# Synch_Demod.net
KiCad netlist of a schematic drawn in Altium Designer
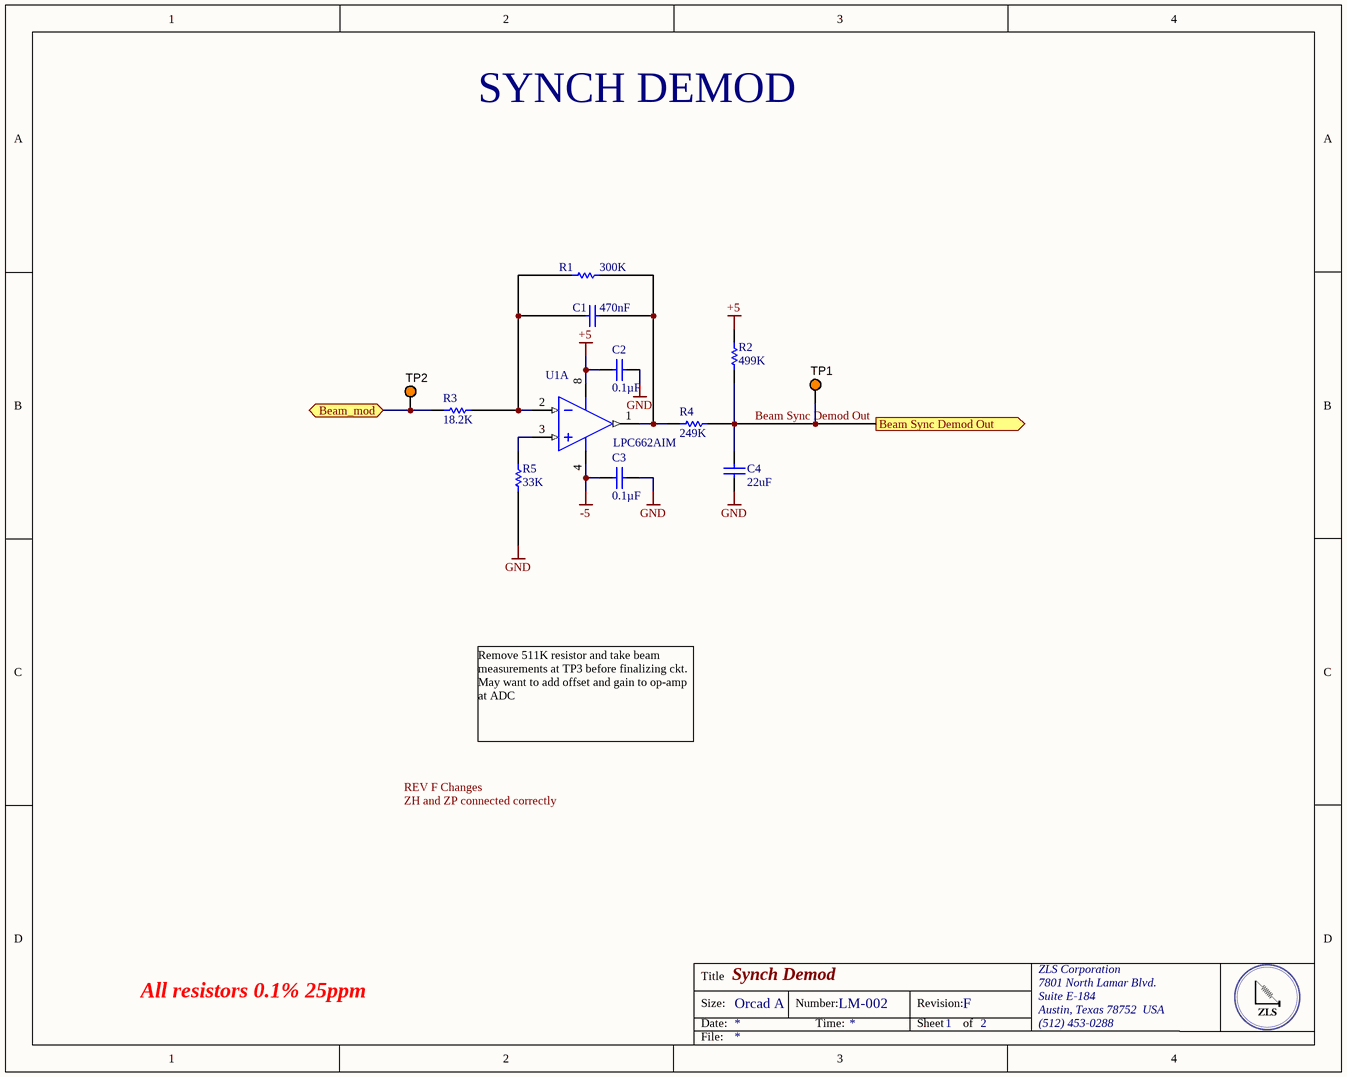
[diagram p0: Synch_Demod.SchDoc]

(export (version "E")
  (design (tool "Eeschema 10.0.6"))
  (components
    (comp (ref "C1")
      (value "470nF")
      (footprint "CAPC0805(2012)75_L")
      (description "CAP CER 0.47UF 25V X7R 0805")
      (fields
        (field (name "MANUFACTURER") "Murata Electronics North America")
        (field (name "MANUFACTURER PART NUMBER") "GRM219R71E474KA88D")
      )
      (libsource (lib "Altium Content Vault") (part "CMP-1036-02117-1"))
    )
    (comp (ref "C2")
      (value "CAP CER 0.1UF 25V X7R 0805")
      (footprint "CAPC0805(2012)145_N")
      (fields
        (field (name "MANUFACTURER") "Murata Electronics North America")
        (field (name "MANUFACTURER PART NUMBER") "GRM21BR71E104KA01L")
        (field (name "CAPACITANCE") "0.1µF")
        (field (name "TOLERANCE") "±10%")
      )
      (libsource (lib "Altium Content Vault") (part "CMP-1036-04795-1"))
    )
    (comp (ref "C3")
      (value "CAP CER 0.1UF 25V X7R 0805")
      (footprint "CAPC0805(2012)145_N")
      (fields
        (field (name "MANUFACTURER") "Murata Electronics North America")
        (field (name "MANUFACTURER PART NUMBER") "GRM21BR71E104KA01L")
        (field (name "CAPACITANCE") "0.1µF")
        (field (name "TOLERANCE") "±10%")
      )
      (libsource (lib "Altium Content Vault") (part "CMP-1036-04795-1"))
    )
    (comp (ref "C4")
      (value "22uF")
      (footprint "CAPC0805(2012)75_L")
      (description "CAP CER 22UF 25V X5R 0805")
      (fields
        (field (name "MANUFACTURER") "Murata Electronics North America")
        (field (name "MANUFACTURER PART NUMBER") "GRM21BR61E226ME44L")
      )
      (libsource (lib "Altium Content Vault") (part "CMP-1036-02117-1"))
    )
    (comp (ref "R1")
      (value "300K")
      (footprint "RESC0805(2012)_L")
      (description "RES SMD 300K OHM 1% 1/8W 0805")
      (fields
        (field (name "MANUFACTURER") "Vishay Dale")
        (field (name "MANUFACTURER PART NUMBER") "CRCW0805300KFKEAHP")
      )
      (libsource (lib "Altium Content Vault") (part "CMP-1013-00215-1"))
    )
    (comp (ref "R2")
      (value "499K")
      (footprint "RESC0805(2012)_L")
      (description "RES SMD 499K OHM 0.1% 1/8W 0805")
      (fields
        (field (name "MANUFACTURER") "Panasonic Electronic Components")
        (field (name "MANUFACTURER PART NUMBER") "ERA-6AEB4993V")
      )
      (libsource (lib "Altium Content Vault") (part "CMP-1013-00215-1"))
    )
    (comp (ref "R3")
      (value "18.2K")
      (footprint "RESC0805(2012)_L")
      (description "RES SMD 18.2K OHM 1% 1/8W 0805")
      (fields
        (field (name "MANUFACTURER") "Panasonic Electronic Components")
        (field (name "MANUFACTURER PART NUMBER") "ERJ-6ENF1822V")
      )
      (libsource (lib "Altium Content Vault") (part "CMP-1013-00215-1"))
    )
    (comp (ref "R4")
      (value "249K")
      (footprint "RESC0805(2012)_L")
      (description "RES SMD 249K OHM 0.1% 1/8W 0805")
      (fields
        (field (name "MANUFACTURER") "Panasonic Electronic Components")
        (field (name "MANUFACTURER PART NUMBER") "ERA-6AEB2493V")
      )
      (libsource (lib "Altium Content Vault") (part "CMP-1013-00215-1"))
    )
    (comp (ref "R5")
      (value "33K")
      (footprint "RESC0805(2012)_L")
      (description "RES SMD 33K OHM 1% 1/2W 0805")
      (fields
        (field (name "MANUFACTURER") "Vishay Dale")
        (field (name "MANUFACTURER PART NUMBER") "CRCW080533K0FKEAHP")
      )
      (libsource (lib "Altium Content Vault") (part "CMP-1013-00215-1"))
    )
    (comp (ref "TP1")
      (value "5003")
      (footprint "KSTN-5003")
      (description "Test Point, Orange, 1-Pin THD, RoHS")
      (libsource (lib "Altium Content Vault") (part "CMP-1672-00009-1"))
    )
    (comp (ref "TP2")
      (value "5003")
      (footprint "KSTN-5003")
      (description "Test Point, Orange, 1-Pin THD, RoHS")
      (libsource (lib "Altium Content Vault") (part "CMP-1672-00009-1"))
    )
    (comp (ref "U1")
      (value "LPC662AIM")
      (footprint "D0008A_M")
      (description "Low Power CMOS Dual Operational Amplifier, 8-pin Narrow SOIC")
      (fields
        (field (name "MANUFACTURER") "Texas Instruments")
        (field (name "MANUFACTURER PART NUMBER") "LPC662AIM/NOPB")
      )
      (libsource (lib "Altium Content Vault") (part "CMP-0055-00867-3"))
    )
  )
  (nets
    (net (code "1") (name "+5") (class "Default")
      (node (ref "C2") (pin "1") (pinfunction "1_1") (pintype "passive"))
      (node (ref "R2") (pin "2") (pinfunction "2_2") (pintype "passive"))
      (node (ref "U1") (pin "8") (pinfunction "V+_8") (pintype "power_in"))
    )
    (net (code "2") (name "-5") (class "Default")
      (node (ref "C3") (pin "1") (pinfunction "1_1") (pintype "passive"))
      (node (ref "U1") (pin "4") (pinfunction "V-_4") (pintype "power_in"))
    )
    (net (code "3") (name "/Beam Sync Demod Out") (class "Default")
      (node (ref "C4") (pin "2") (pinfunction "2_2") (pintype "passive"))
      (node (ref "R2") (pin "1") (pinfunction "1_1") (pintype "passive"))
      (node (ref "R4") (pin "1") (pinfunction "1_1") (pintype "passive"))
      (node (ref "TP1") (pin "1") (pinfunction "1_1") (pintype "passive"))
    )
    (net (code "4") (name "/Beam_mod") (class "Default")
      (node (ref "R3") (pin "2") (pinfunction "2_2") (pintype "passive"))
      (node (ref "TP2") (pin "1") (pinfunction "1_1") (pintype "passive"))
    )
    (net (code "7") (name "GND") (class "Default")
      (node (ref "C2") (pin "2") (pinfunction "2_2") (pintype "passive"))
      (node (ref "C3") (pin "2") (pinfunction "2_2") (pintype "passive"))
      (node (ref "C4") (pin "1") (pinfunction "1_1") (pintype "passive"))
      (node (ref "R5") (pin "1") (pinfunction "1_1") (pintype "passive"))
    )
    (net (code "8") (name "Net-(U1A-INA+)") (class "Default")
      (node (ref "R5") (pin "2") (pinfunction "2_2") (pintype "passive"))
      (node (ref "U1") (pin "3") (pinfunction "INA+_3") (pintype "input"))
    )
    (net (code "9") (name "Net-(U1A-INA-)") (class "Default")
      (node (ref "C1") (pin "1") (pinfunction "1_1") (pintype "passive"))
      (node (ref "R1") (pin "2") (pinfunction "2_2") (pintype "passive"))
      (node (ref "R3") (pin "1") (pinfunction "1_1") (pintype "passive"))
      (node (ref "U1") (pin "2") (pinfunction "INA-_2") (pintype "input"))
    )
    (net (code "10") (name "Net-(U1A-OUTA)") (class "Default")
      (node (ref "C1") (pin "2") (pinfunction "2_2") (pintype "passive"))
      (node (ref "R1") (pin "1") (pinfunction "1_1") (pintype "passive"))
      (node (ref "R4") (pin "2") (pinfunction "2_2") (pintype "passive"))
      (node (ref "U1") (pin "1") (pinfunction "OUTA_1") (pintype "output"))
    )
  )
)
